# DVI.net
KiCad netlist of a schematic drawn in EAGLE
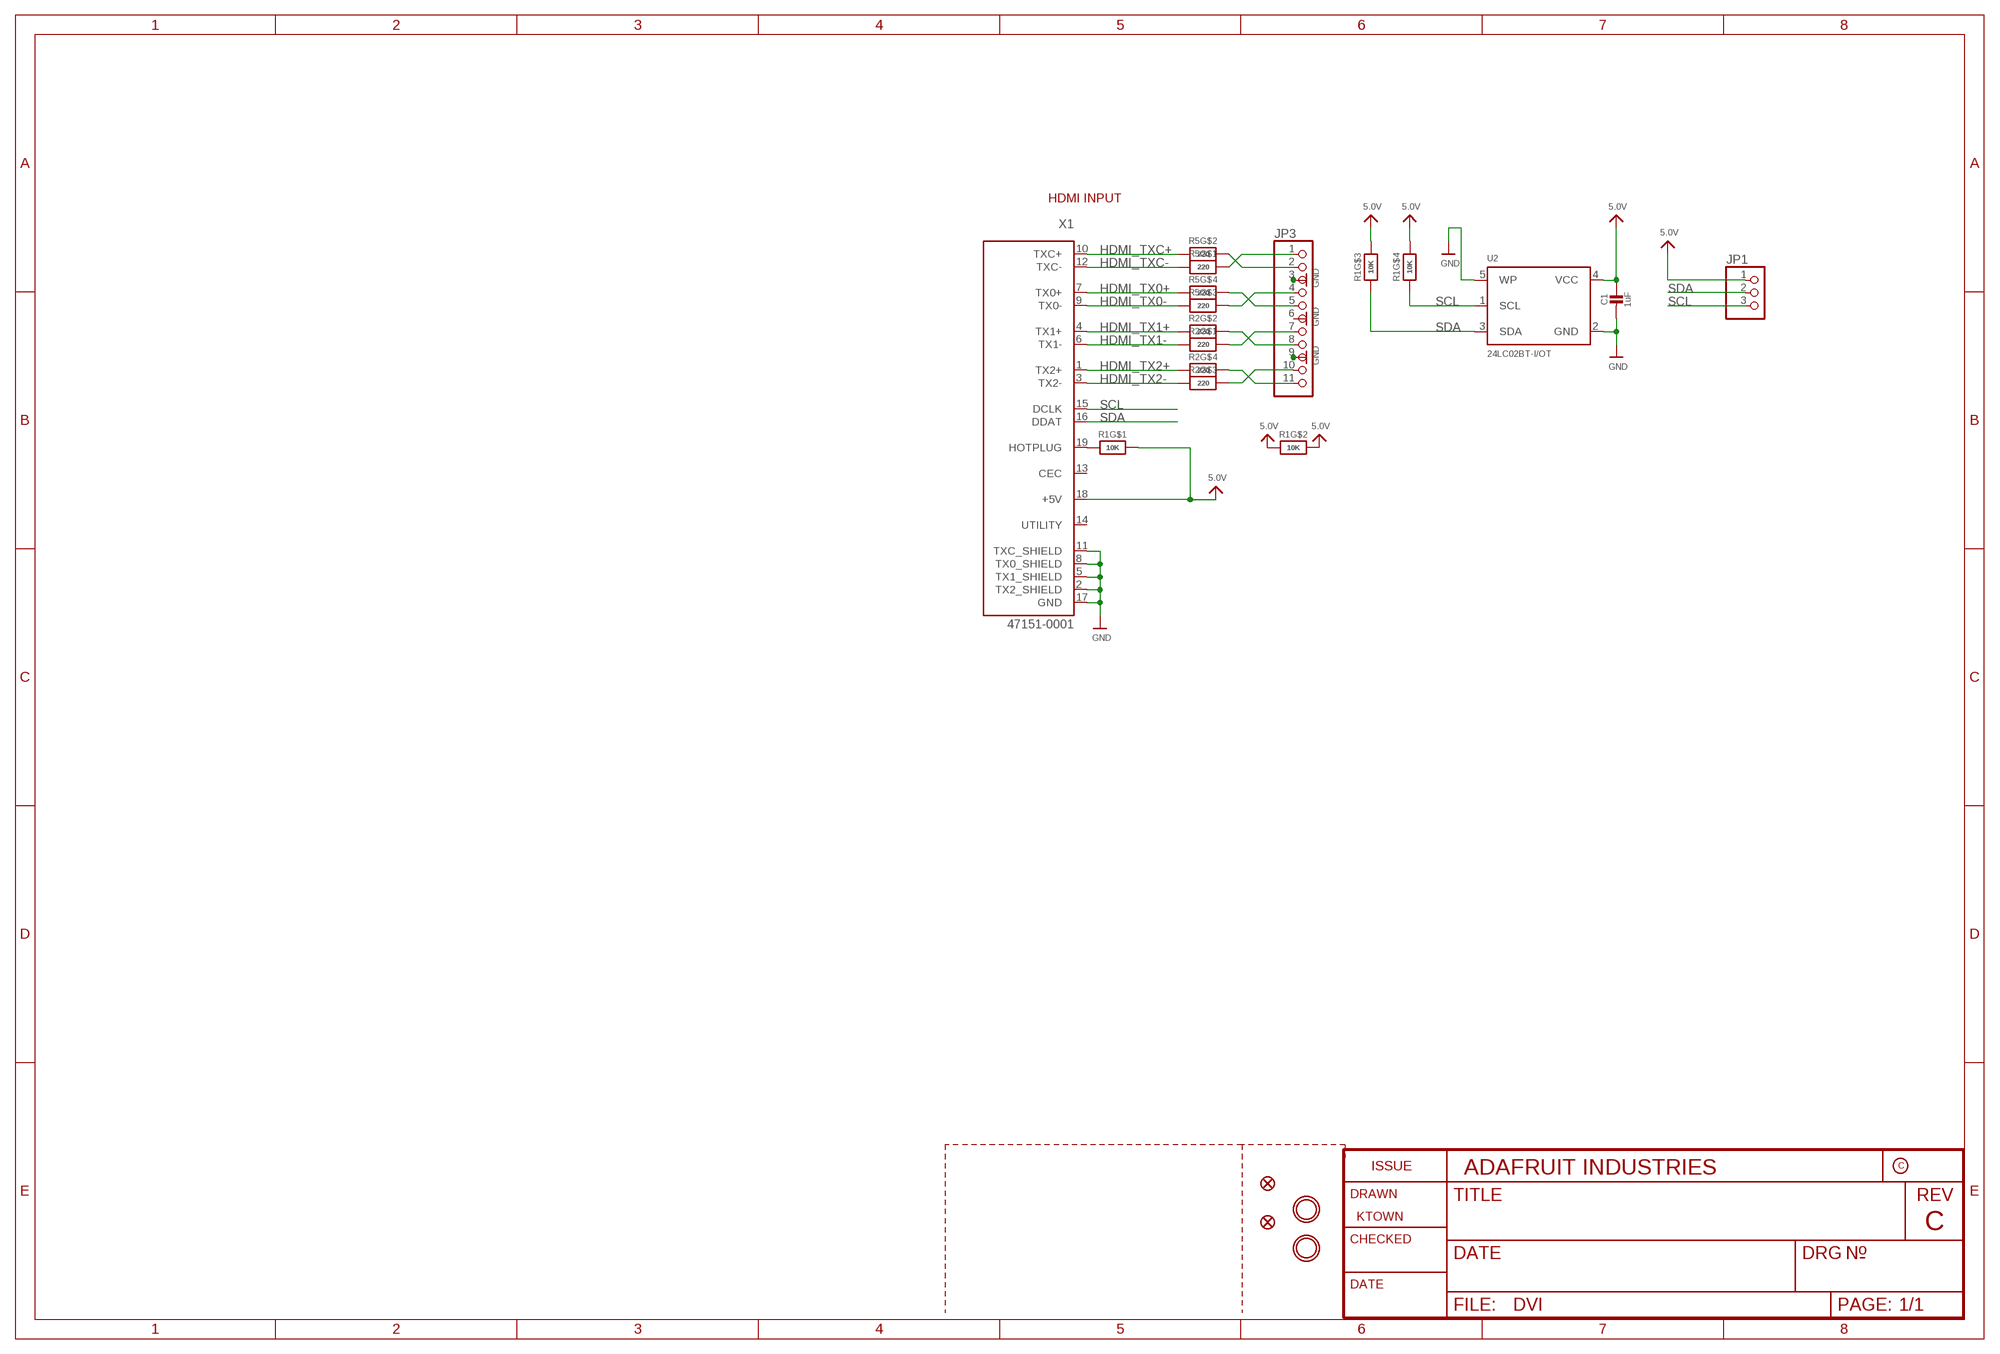
[diagram p0: schematic, sheet 1]

(export (version "E")
  (design (tool "Eeschema 10.0.6"))
  (components
    (comp (ref "C1")
      (value "1uF")
      (footprint "eagle-import:0603-NO")
      (libsource (lib "eagle-import") (part "CAP_CERAMIC0603_NO"))
    )
    (comp (ref "FID1")
      (value "FIDUCIAL_1MM")
      (footprint "eagle-import:FIDUCIAL_1MM")
      (libsource (lib "eagle-import") (part "FIDUCIAL_1MM"))
    )
    (comp (ref "FID2")
      (value "FIDUCIAL_1MM")
      (footprint "eagle-import:FIDUCIAL_1MM")
      (libsource (lib "eagle-import") (part "FIDUCIAL_1MM"))
    )
    (comp (ref "JP1")
      (value "HEADER-1X3ROUND")
      (footprint "eagle-import:1X03_ROUND")
      (libsource (lib "eagle-import") (part "HEADER-1X3ROUND"))
    )
    (comp (ref "JP3")
      (value "HEADER-1X11")
      (footprint "eagle-import:1X11_ROUND")
      (libsource (lib "eagle-import") (part "HEADER-1X11"))
    )
    (comp (ref "R1")
      (value "10K")
      (footprint "eagle-import:RESPACK_4X0603")
      (libsource (lib "eagle-import") (part "RESISTOR_4PACK"))
    )
    (comp (ref "R2")
      (value "220")
      (footprint "eagle-import:RESPACK_4X0603")
      (libsource (lib "eagle-import") (part "RESISTOR_4PACK"))
    )
    (comp (ref "R5")
      (value "220")
      (footprint "eagle-import:RESPACK_4X0603")
      (libsource (lib "eagle-import") (part "RESISTOR_4PACK"))
    )
    (comp (ref "U$32")
      (value "MOUNTINGHOLE2.5")
      (footprint "eagle-import:MOUNTINGHOLE_2.5_PLATED")
      (libsource (lib "eagle-import") (part "MOUNTINGHOLE2.5"))
    )
    (comp (ref "U$33")
      (value "MOUNTINGHOLE2.5")
      (footprint "eagle-import:MOUNTINGHOLE_2.5_PLATED")
      (libsource (lib "eagle-import") (part "MOUNTINGHOLE2.5"))
    )
    (comp (ref "U2")
      (value "24LC02BT-I/OT")
      (footprint "eagle-import:SOT23-5")
      (libsource (lib "eagle-import") (part "EEPROM_I2C_MCP24AA32"))
    )
    (comp (ref "X1")
      (value "47151-0001")
      (footprint "eagle-import:HDMI_MOLEX_47151-0001")
      (libsource (lib "eagle-import") (part "HDMI_MOLEX_47151"))
    )
  )
  (nets
    (net (code "1") (name "/HDMI_TX0+") (class "Default")
      (node (ref "R5") (pin "4") (pinfunction "1_4") (pintype "passive"))
      (node (ref "X1") (pin "7") (pinfunction "TX0+_7") (pintype "bidirectional"))
    )
    (net (code "2") (name "/HDMI_TX0-") (class "Default")
      (node (ref "R5") (pin "3") (pinfunction "1_3") (pintype "passive"))
      (node (ref "X1") (pin "9") (pinfunction "TX0-_9") (pintype "bidirectional"))
    )
    (net (code "3") (name "/HDMI_TX1+") (class "Default")
      (node (ref "R2") (pin "2") (pinfunction "1_2") (pintype "passive"))
      (node (ref "X1") (pin "4") (pinfunction "TX1+_4") (pintype "bidirectional"))
    )
    (net (code "4") (name "/HDMI_TX1-") (class "Default")
      (node (ref "R2") (pin "1") (pinfunction "1_1") (pintype "passive"))
      (node (ref "X1") (pin "6") (pinfunction "TX1-_6") (pintype "bidirectional"))
    )
    (net (code "5") (name "/HDMI_TX2+") (class "Default")
      (node (ref "R2") (pin "4") (pinfunction "1_4") (pintype "passive"))
      (node (ref "X1") (pin "1") (pinfunction "TX2+_1") (pintype "bidirectional"))
    )
    (net (code "6") (name "/HDMI_TX2-") (class "Default")
      (node (ref "R2") (pin "3") (pinfunction "1_3") (pintype "passive"))
      (node (ref "X1") (pin "3") (pinfunction "TX2-_3") (pintype "bidirectional"))
    )
    (net (code "7") (name "/HDMI_TXC+") (class "Default")
      (node (ref "R5") (pin "2") (pinfunction "1_2") (pintype "passive"))
      (node (ref "X1") (pin "10") (pinfunction "TXC+_10") (pintype "bidirectional"))
    )
    (net (code "8") (name "/HDMI_TXC-") (class "Default")
      (node (ref "R5") (pin "1") (pinfunction "1_1") (pintype "passive"))
      (node (ref "X1") (pin "12") (pinfunction "TXC-_12") (pintype "bidirectional"))
    )
    (net (code "9") (name "/SCL") (class "Default")
      (node (ref "JP1") (pin "3") (pinfunction "3_3") (pintype "passive"))
      (node (ref "R1") (pin "4") (pinfunction "1_4") (pintype "passive"))
      (node (ref "U2") (pin "1") (pinfunction "SCL_1") (pintype "bidirectional"))
      (node (ref "X1") (pin "15") (pinfunction "DCLK_15") (pintype "bidirectional"))
    )
    (net (code "10") (name "/SDA") (class "Default")
      (node (ref "JP1") (pin "2") (pinfunction "2_2") (pintype "passive"))
      (node (ref "R1") (pin "3") (pinfunction "1_3") (pintype "passive"))
      (node (ref "U2") (pin "3") (pinfunction "SDA_3") (pintype "bidirectional"))
      (node (ref "X1") (pin "16") (pinfunction "DDAT_16") (pintype "bidirectional"))
    )
    (net (code "11") (name "5.0V") (class "Default")
      (node (ref "C1") (pin "1") (pinfunction "1_1") (pintype "passive"))
      (node (ref "JP1") (pin "1") (pinfunction "1_1") (pintype "passive"))
      (node (ref "R1") (pin "2") (pinfunction "1_2") (pintype "passive"))
      (node (ref "R1") (pin "5") (pinfunction "2_5") (pintype "passive"))
      (node (ref "R1") (pin "6") (pinfunction "2_6") (pintype "passive"))
      (node (ref "R1") (pin "7") (pinfunction "2_7") (pintype "passive"))
      (node (ref "R1") (pin "8") (pinfunction "2_8") (pintype "passive"))
      (node (ref "U2") (pin "4") (pinfunction "VCC_4") (pintype "bidirectional"))
      (node (ref "X1") (pin "18") (pinfunction "+5V_18") (pintype "power_in"))
    )
    (net (code "12") (name "GND") (class "Default")
      (node (ref "C1") (pin "2") (pinfunction "2_2") (pintype "passive"))
      (node (ref "JP3") (pin "3") (pinfunction "3_3") (pintype "passive"))
      (node (ref "JP3") (pin "6") (pinfunction "6_6") (pintype "passive"))
      (node (ref "JP3") (pin "9") (pinfunction "9_9") (pintype "passive"))
      (node (ref "U2") (pin "2") (pinfunction "GND_2") (pintype "bidirectional"))
      (node (ref "U2") (pin "5") (pinfunction "WP_5") (pintype "bidirectional"))
      (node (ref "X1") (pin "11") (pinfunction "TXC_SHIELD_11") (pintype "power_in"))
      (node (ref "X1") (pin "17") (pinfunction "GND_17") (pintype "power_in"))
      (node (ref "X1") (pin "2") (pinfunction "TX2_SHIELD_2") (pintype "power_in"))
      (node (ref "X1") (pin "5") (pinfunction "TX1_SHIELD_5") (pintype "power_in"))
      (node (ref "X1") (pin "8") (pinfunction "TX0_SHIELD_8") (pintype "power_in"))
    )
    (net (code "13") (name "Net-(R2A-2)") (class "Default")
      (node (ref "JP3") (pin "7") (pinfunction "7_7") (pintype "passive"))
      (node (ref "R2") (pin "8") (pinfunction "2_8") (pintype "passive"))
    )
    (net (code "14") (name "Net-(R2B-2)") (class "Default")
      (node (ref "JP3") (pin "8") (pinfunction "8_8") (pintype "passive"))
      (node (ref "R2") (pin "7") (pinfunction "2_7") (pintype "passive"))
    )
    (net (code "15") (name "Net-(R2C-2)") (class "Default")
      (node (ref "JP3") (pin "10") (pinfunction "10_10") (pintype "passive"))
      (node (ref "R2") (pin "6") (pinfunction "2_6") (pintype "passive"))
    )
    (net (code "16") (name "Net-(R2D-2)") (class "Default")
      (node (ref "JP3") (pin "11") (pinfunction "11_11") (pintype "passive"))
      (node (ref "R2") (pin "5") (pinfunction "2_5") (pintype "passive"))
    )
    (net (code "17") (name "Net-(R5A-2)") (class "Default")
      (node (ref "JP3") (pin "1") (pinfunction "1_1") (pintype "passive"))
      (node (ref "R5") (pin "8") (pinfunction "2_8") (pintype "passive"))
    )
    (net (code "18") (name "Net-(R5B-2)") (class "Default")
      (node (ref "JP3") (pin "2") (pinfunction "2_2") (pintype "passive"))
      (node (ref "R5") (pin "7") (pinfunction "2_7") (pintype "passive"))
    )
    (net (code "19") (name "Net-(R5C-2)") (class "Default")
      (node (ref "JP3") (pin "4") (pinfunction "4_4") (pintype "passive"))
      (node (ref "R5") (pin "6") (pinfunction "2_6") (pintype "passive"))
    )
    (net (code "20") (name "Net-(R5D-2)") (class "Default")
      (node (ref "JP3") (pin "5") (pinfunction "5_5") (pintype "passive"))
      (node (ref "R5") (pin "5") (pinfunction "2_5") (pintype "passive"))
    )
    (net (code "21") (name "Net-(X1A-HOTPLUG)") (class "Default")
      (node (ref "R1") (pin "1") (pinfunction "1_1") (pintype "passive"))
      (node (ref "X1") (pin "19") (pinfunction "HOTPLUG_19") (pintype "bidirectional"))
    )
    (net (code "22") (name "unconnected-(X1A-CEC-Pad13)") (class "Default")
      (node (ref "X1") (pin "13") (pinfunction "CEC_13") (pintype "bidirectional"))
    )
    (net (code "23") (name "unconnected-(X1A-UTILITY-Pad14)") (class "Default")
      (node (ref "X1") (pin "14") (pinfunction "UTILITY_14") (pintype "bidirectional"))
    )
  )
)
